# ADCS.net
KiCad netlist of a schematic drawn in Altium Designer
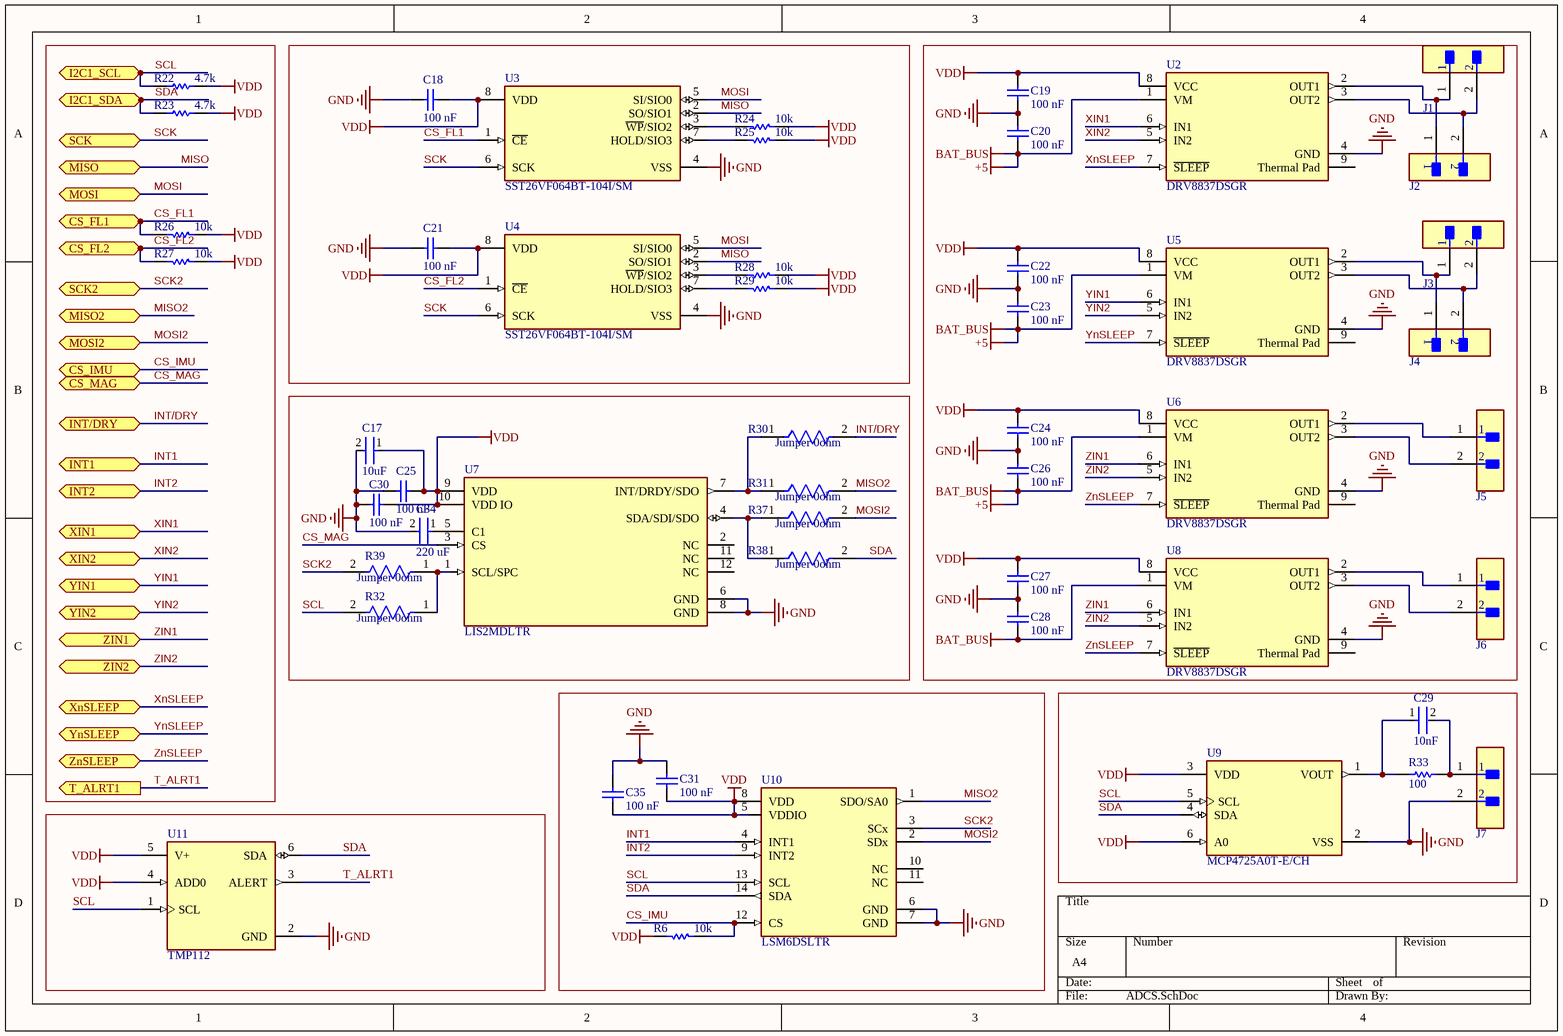
[diagram p0: ADCS.SchDoc]

(export (version "E")
  (design (tool "Eeschema 10.0.6"))
  (components
    (comp (ref "C17")
      (value "10uF")
      (footprint "FP-CL21B106KOQNNNG-MFG")
      (description "CAP CER 10UF 16V X7R 0805")
      (fields (field (name "TOLERANCE") "10%") (field (name "MANUFACTURER PART NUMBER") "CL21B106KOQNNNG"))
      (libsource (lib "Altium Content Vault") (part "b4654b650e69147ec39a6b967a45e02"))
    )
    (comp (ref "C18")
      (value "100 nF")
      (footprint "CAPC1050X55X23ML05T13")
      (description "Chip Capacitor, 100 nF, +/- 10%, 16 V, -55 to 125 degC, 0402 (1005 Metric), RoHS, Tape and Reel")
      (fields (field (name "MANUFACTURER") "Samsung Electro-Mechanics"))
      (libsource (lib "Altium Content Vault") (part "CAP-NP-2"))
    )
    (comp (ref "C19")
      (value "100 nF")
      (footprint "CAPC1050X55X23ML05T13")
      (description "Chip Capacitor, 100 nF, +/- 10%, 16 V, -55 to 125 degC, 0402 (1005 Metric), RoHS, Tape and Reel")
      (fields (field (name "MANUFACTURER") "Samsung Electro-Mechanics"))
      (libsource (lib "Altium Content Vault") (part "CAP-NP-2"))
    )
    (comp (ref "C20")
      (value "100 nF")
      (footprint "CAPC1050X55X23ML05T13")
      (description "Chip Capacitor, 100 nF, +/- 10%, 16 V, -55 to 125 degC, 0402 (1005 Metric), RoHS, Tape and Reel")
      (fields (field (name "MANUFACTURER") "Samsung Electro-Mechanics"))
      (libsource (lib "Altium Content Vault") (part "CAP-NP-2"))
    )
    (comp (ref "C21")
      (value "100 nF")
      (footprint "CAPC1050X55X23ML05T13")
      (description "Chip Capacitor, 100 nF, +/- 10%, 16 V, -55 to 125 degC, 0402 (1005 Metric), RoHS, Tape and Reel")
      (fields (field (name "MANUFACTURER") "Samsung Electro-Mechanics"))
      (libsource (lib "Altium Content Vault") (part "CAP-NP-2"))
    )
    (comp (ref "C22")
      (value "100 nF")
      (footprint "CAPC1050X55X23ML05T13")
      (description "Chip Capacitor, 100 nF, +/- 10%, 16 V, -55 to 125 degC, 0402 (1005 Metric), RoHS, Tape and Reel")
      (fields (field (name "MANUFACTURER") "Samsung Electro-Mechanics"))
      (libsource (lib "Altium Content Vault") (part "CAP-NP-2"))
    )
    (comp (ref "C23")
      (value "100 nF")
      (footprint "CAPC1050X55X23ML05T13")
      (description "Chip Capacitor, 100 nF, +/- 10%, 16 V, -55 to 125 degC, 0402 (1005 Metric), RoHS, Tape and Reel")
      (fields (field (name "MANUFACTURER") "Samsung Electro-Mechanics"))
      (libsource (lib "Altium Content Vault") (part "CAP-NP-2"))
    )
    (comp (ref "C24")
      (value "100 nF")
      (footprint "CAPC1050X55X23ML05T13")
      (description "Chip Capacitor, 100 nF, +/- 10%, 16 V, -55 to 125 degC, 0402 (1005 Metric), RoHS, Tape and Reel")
      (fields (field (name "MANUFACTURER") "Samsung Electro-Mechanics"))
      (libsource (lib "Altium Content Vault") (part "CAP-NP-2"))
    )
    (comp (ref "C25")
      (value "100 nF")
      (footprint "CAPC1050X55X23ML05T13")
      (description "Chip Capacitor, 100 nF, +/- 10%, 16 V, -55 to 125 degC, 0402 (1005 Metric), RoHS, Tape and Reel")
      (fields (field (name "MANUFACTURER") "Samsung Electro-Mechanics"))
      (libsource (lib "Altium Content Vault") (part "CAP-NP-2"))
    )
    (comp (ref "C26")
      (value "100 nF")
      (footprint "CAPC1050X55X23ML05T13")
      (description "Chip Capacitor, 100 nF, +/- 10%, 16 V, -55 to 125 degC, 0402 (1005 Metric), RoHS, Tape and Reel")
      (fields (field (name "MANUFACTURER") "Samsung Electro-Mechanics"))
      (libsource (lib "Altium Content Vault") (part "CAP-NP-2"))
    )
    (comp (ref "C27")
      (value "100 nF")
      (footprint "CAPC1050X55X23ML05T13")
      (description "Chip Capacitor, 100 nF, +/- 10%, 16 V, -55 to 125 degC, 0402 (1005 Metric), RoHS, Tape and Reel")
      (fields (field (name "MANUFACTURER") "Samsung Electro-Mechanics"))
      (libsource (lib "Altium Content Vault") (part "CAP-NP-2"))
    )
    (comp (ref "C28")
      (value "100 nF")
      (footprint "CAPC1050X55X23ML05T13")
      (description "Chip Capacitor, 100 nF, +/- 10%, 16 V, -55 to 125 degC, 0402 (1005 Metric), RoHS, Tape and Reel")
      (fields (field (name "MANUFACTURER") "Samsung Electro-Mechanics"))
      (libsource (lib "Altium Content Vault") (part "CAP-NP-2"))
    )
    (comp (ref "C29")
      (value "10nF")
      (footprint "FP-CL165-IPC_C")
      (description "Cap Ceramic 10nF 50V X7R ±10% SMD 0402 +125°C Paper T/R")
      (fields (field (name "VOLTAGE") "50V") (field (name "TOLERANCE") "10%"))
      (libsource (lib "Altium Content Vault") (part "b4654b650e69147ec39a6b967a45e02"))
    )
    (comp (ref "C30")
      (value "100 nF")
      (footprint "CAPC1050X55X23ML05T13")
      (description "Chip Capacitor, 100 nF, +/- 10%, 16 V, -55 to 125 degC, 0402 (1005 Metric), RoHS, Tape and Reel")
      (fields (field (name "MANUFACTURER") "Samsung Electro-Mechanics"))
      (libsource (lib "Altium Content Vault") (part "CAP-NP-2"))
    )
    (comp (ref "C31")
      (value "100 nF")
      (footprint "CAPC1050X55X23ML05T13")
      (description "Chip Capacitor, 100 nF, +/- 10%, 16 V, -55 to 125 degC, 0402 (1005 Metric), RoHS, Tape and Reel")
      (fields (field (name "MANUFACTURER") "Samsung Electro-Mechanics"))
      (libsource (lib "Altium Content Vault") (part "CAP-NP-2"))
    )
    (comp (ref "C34")
      (value "220 uF")
      (footprint "FP-C0603C-CF-MFG")
      (description "CAP CER 0603 .22UF 10V X7R 20% A")
      (fields (field (name "TOLERANCE") "0.2") (field (name "MANUFACTURER PART NUMBER") "C0603C224M8RACAUTO"))
      (libsource (lib "Altium Content Vault") (part "b4654b650e69147ec39a6b967a45e02"))
    )
    (comp (ref "C35")
      (value "100 nF")
      (footprint "CAPC1050X55X23ML05T13")
      (description "Chip Capacitor, 100 nF, +/- 10%, 16 V, -55 to 125 degC, 0402 (1005 Metric), RoHS, Tape and Reel")
      (fields (field (name "MANUFACTURER") "Samsung Electro-Mechanics"))
      (libsource (lib "Altium Content Vault") (part "CAP-NP-2"))
    )
    (comp (ref "J1")
      (value "B2B-XH-A(LF)(SN)")
      (footprint "FP-B2B-XH-A_LF_SN-MFG")
      (description "CONN HEADER VERT 2POS 2.5MM")
      (libsource (lib "") (part "3bc925449376181038e59eaffc5286c_1"))
    )
    (comp (ref "J2")
      (value "B2B-XH-A(LF)(SN)")
      (footprint "FP-B2B-XH-A_LF_SN-MFG")
      (description "CONN HEADER VERT 2POS 2.5MM")
      (libsource (lib "") (part "3bc925449376181038e59eaffc5286c_2"))
    )
    (comp (ref "J3")
      (value "B2B-XH-A(LF)(SN)")
      (footprint "FP-B2B-XH-A_LF_SN-MFG")
      (description "CONN HEADER VERT 2POS 2.5MM")
      (libsource (lib "") (part "3bc925449376181038e59eaffc5286c_1"))
    )
    (comp (ref "J4")
      (value "B2B-XH-A(LF)(SN)")
      (footprint "FP-B2B-XH-A_LF_SN-MFG")
      (description "CONN HEADER VERT 2POS 2.5MM")
      (libsource (lib "") (part "3bc925449376181038e59eaffc5286c_2"))
    )
    (comp (ref "J5")
      (value "B2B-XH-A(LF)(SN)")
      (footprint "FP-B2B-XH-A_LF_SN-MFG")
      (description "CONN HEADER VERT 2POS 2.5MM")
      (libsource (lib "Altium Content Vault") (part "3bc925449376181038e59eaffc5286c"))
    )
    (comp (ref "J6")
      (value "B2B-XH-A(LF)(SN)")
      (footprint "FP-B2B-XH-A_LF_SN-MFG")
      (description "CONN HEADER VERT 2POS 2.5MM")
      (libsource (lib "Altium Content Vault") (part "3bc925449376181038e59eaffc5286c"))
    )
    (comp (ref "J7")
      (value "B2B-XH-A(LF)(SN)")
      (footprint "FP-B2B-XH-A_LF_SN-MFG")
      (description "CONN HEADER VERT 2POS 2.5MM")
      (libsource (lib "Altium Content Vault") (part "3bc925449376181038e59eaffc5286c"))
    )
    (comp (ref "R6")
      (value "10k")
      (footprint "RESC1005X40X25LL05T05")
      (description "Chip Resistor, 10 KOhm, +/- 1%, 0.1 W, -55 to 155 degC, 0402 (1005 Metric), RoHS, Tape and Reel")
      (fields (field (name "TOLERANCE") "1%") (field (name "MANUFACTURER") "Panasonic"))
      (libsource (lib "Altium Content Vault") (part "RES-2"))
    )
    (comp (ref "R22")
      (value "4.7k")
      (footprint "RESC1005X40X25LL05T05")
      (description "Chip Resistor, 4.7 KOhm, +/- 1%, 0.1 W, -55 to 155 degC, 0402 (1005 Metric), RoHS, Tape and Reel")
      (fields (field (name "TOLERANCE") "1%") (field (name "PARTNUMBER") "ERJ-2RKF4701X"))
      (libsource (lib "Altium Content Vault") (part "RES-2"))
    )
    (comp (ref "R23")
      (value "4.7k")
      (footprint "RESC1005X40X25LL05T05")
      (description "Chip Resistor, 4.7 KOhm, +/- 1%, 0.1 W, -55 to 155 degC, 0402 (1005 Metric), RoHS, Tape and Reel")
      (fields (field (name "TOLERANCE") "1%") (field (name "PARTNUMBER") "ERJ-2RKF4701X"))
      (libsource (lib "Altium Content Vault") (part "RES-2"))
    )
    (comp (ref "R24")
      (value "10k")
      (footprint "RESC1005X40X25LL05T05")
      (description "Chip Resistor, 10 KOhm, +/- 1%, 0.1 W, -55 to 155 degC, 0402 (1005 Metric), RoHS, Tape and Reel")
      (fields (field (name "TOLERANCE") "1%") (field (name "MANUFACTURER") "Panasonic"))
      (libsource (lib "Altium Content Vault") (part "RES-2"))
    )
    (comp (ref "R25")
      (value "10k")
      (footprint "RESC1005X40X25LL05T05")
      (description "Chip Resistor, 10 KOhm, +/- 1%, 0.1 W, -55 to 155 degC, 0402 (1005 Metric), RoHS, Tape and Reel")
      (fields (field (name "TOLERANCE") "1%") (field (name "MANUFACTURER") "Panasonic"))
      (libsource (lib "Altium Content Vault") (part "RES-2"))
    )
    (comp (ref "R26")
      (value "10k")
      (footprint "RESC1005X40X25LL05T05")
      (description "Chip Resistor, 10 KOhm, +/- 1%, 0.1 W, -55 to 155 degC, 0402 (1005 Metric), RoHS, Tape and Reel")
      (fields (field (name "TOLERANCE") "1%") (field (name "MANUFACTURER") "Panasonic"))
      (libsource (lib "Altium Content Vault") (part "RES-2"))
    )
    (comp (ref "R27")
      (value "10k")
      (footprint "RESC1005X40X25LL05T05")
      (description "Chip Resistor, 10 KOhm, +/- 1%, 0.1 W, -55 to 155 degC, 0402 (1005 Metric), RoHS, Tape and Reel")
      (fields (field (name "TOLERANCE") "1%") (field (name "MANUFACTURER") "Panasonic"))
      (libsource (lib "Altium Content Vault") (part "RES-2"))
    )
    (comp (ref "R28")
      (value "10k")
      (footprint "RESC1005X40X25LL05T05")
      (description "Chip Resistor, 10 KOhm, +/- 1%, 0.1 W, -55 to 155 degC, 0402 (1005 Metric), RoHS, Tape and Reel")
      (fields (field (name "TOLERANCE") "1%") (field (name "MANUFACTURER") "Panasonic"))
      (libsource (lib "Altium Content Vault") (part "RES-2"))
    )
    (comp (ref "R29")
      (value "10k")
      (footprint "RESC1005X40X25LL05T05")
      (description "Chip Resistor, 10 KOhm, +/- 1%, 0.1 W, -55 to 155 degC, 0402 (1005 Metric), RoHS, Tape and Reel")
      (fields (field (name "TOLERANCE") "1%") (field (name "MANUFACTURER") "Panasonic"))
      (libsource (lib "Altium Content Vault") (part "RES-2"))
    )
    (comp (ref "R30")
      (value "Jumper 0ohm")
      (footprint "FP-RC1206-MFG")
      (description "RES SMD 0 OHM JUMPER 1/4W 1206")
      (fields
        (field (name "MANUFACTURER PART NUMBER") "RC1206JR-070RL")
        (field (name "MANUFACTURER") "YAGEO")
      )
      (libsource (lib "Altium Content Vault") (part "1029c3af85768c4190bb7ad29bc67b5"))
    )
    (comp (ref "R31")
      (value "Jumper 0ohm")
      (footprint "FP-RC1206-MFG")
      (description "RES SMD 0 OHM JUMPER 1/4W 1206")
      (fields
        (field (name "MANUFACTURER PART NUMBER") "RC1206JR-070RL")
        (field (name "MANUFACTURER") "YAGEO")
      )
      (libsource (lib "Altium Content Vault") (part "1029c3af85768c4190bb7ad29bc67b5"))
    )
    (comp (ref "R32")
      (value "Jumper 0ohm")
      (footprint "FP-RC1206-MFG")
      (description "RES SMD 0 OHM JUMPER 1/4W 1206")
      (fields
        (field (name "MANUFACTURER PART NUMBER") "RC1206JR-070RL")
        (field (name "MANUFACTURER") "YAGEO")
      )
      (libsource (lib "Altium Content Vault") (part "1029c3af85768c4190bb7ad29bc67b5"))
    )
    (comp (ref "R33")
      (value "100")
      (footprint "RESC1608X55X30LL15T15")
      (fields (field (name "MANUFACTURER") "Panasonic") (field (name "PART NUMBER") "ERJ-3EKF1000V"))
      (libsource (lib "Altium Content Vault") (part "RES"))
    )
    (comp (ref "R37")
      (value "Jumper 0ohm")
      (footprint "FP-RC1206-MFG")
      (description "RES SMD 0 OHM JUMPER 1/4W 1206")
      (fields
        (field (name "MANUFACTURER PART NUMBER") "RC1206JR-070RL")
        (field (name "MANUFACTURER") "YAGEO")
      )
      (libsource (lib "Altium Content Vault") (part "1029c3af85768c4190bb7ad29bc67b5"))
    )
    (comp (ref "R38")
      (value "Jumper 0ohm")
      (footprint "FP-RC1206-MFG")
      (description "RES SMD 0 OHM JUMPER 1/4W 1206")
      (fields
        (field (name "MANUFACTURER PART NUMBER") "RC1206JR-070RL")
        (field (name "MANUFACTURER") "YAGEO")
      )
      (libsource (lib "Altium Content Vault") (part "1029c3af85768c4190bb7ad29bc67b5"))
    )
    (comp (ref "R39")
      (value "Jumper 0ohm")
      (footprint "FP-RC1206-MFG")
      (description "RES SMD 0 OHM JUMPER 1/4W 1206")
      (fields
        (field (name "MANUFACTURER PART NUMBER") "RC1206JR-070RL")
        (field (name "MANUFACTURER") "YAGEO")
      )
      (libsource (lib "Altium Content Vault") (part "1029c3af85768c4190bb7ad29bc67b5"))
    )
    (comp (ref "U2")
      (value "DRV8837DSGR")
      (footprint "FP-DSG0008A-MFG")
      (description "IC MOTOR DRIVER PAR 8WSON")
      (fields
        (field (name "MANUFACTURER") "Texas Instruments")
        (field (name "OCTOPART") "https://octopart.com/drv8837dsgr-texas+instruments-23786726")
      )
      (libsource (lib "Altium Content Vault") (part "0edabe62f55b79d65ef7cb8a22a7164"))
    )
    (comp (ref "U3")
      (value "SST26VF064BT-104I/SM")
      (footprint "FP-C04-056-IPC_A")
      (description "IC FLASH 64M SPI 104MHZ 8SOIJ")
      (libsource (lib "Altium Content Vault") (part "6350b331e85e90157e4ee501ce7d1a5"))
    )
    (comp (ref "U4")
      (value "SST26VF064BT-104I/SM")
      (footprint "FP-C04-056-IPC_A")
      (description "IC FLASH 64M SPI 104MHZ 8SOIJ")
      (libsource (lib "Altium Content Vault") (part "6350b331e85e90157e4ee501ce7d1a5"))
    )
    (comp (ref "U5")
      (value "DRV8837DSGR")
      (footprint "FP-DSG0008A-MFG")
      (description "IC MOTOR DRIVER PAR 8WSON")
      (fields
        (field (name "MANUFACTURER") "Texas Instruments")
        (field (name "OCTOPART") "https://octopart.com/drv8837dsgr-texas+instruments-23786726")
      )
      (libsource (lib "Altium Content Vault") (part "0edabe62f55b79d65ef7cb8a22a7164"))
    )
    (comp (ref "U6")
      (value "DRV8837DSGR")
      (footprint "FP-DSG0008A-MFG")
      (description "IC MOTOR DRIVER PAR 8WSON")
      (fields
        (field (name "MANUFACTURER") "Texas Instruments")
        (field (name "OCTOPART") "https://octopart.com/drv8837dsgr-texas+instruments-23786726")
      )
      (libsource (lib "Altium Content Vault") (part "0edabe62f55b79d65ef7cb8a22a7164"))
    )
    (comp (ref "U7")
      (value "LIS2MDLTR")
      (footprint "FP-LGA-12-DM00170568-MFG")
      (description "SENSOR MR I2C/SPI 12LGA")
      (fields
        (field (name "OCTOPART") "https://octopart.com/lis2mdltr-stmicroelectronics-81117311")
        (field (name "MANUFACTURER") "STMicroelectronics")
      )
      (libsource (lib "Altium Content Vault") (part "91637d6a6da3cb2d69b1e7726cd74d2"))
    )
    (comp (ref "U8")
      (value "DRV8837DSGR")
      (footprint "FP-DSG0008A-MFG")
      (description "IC MOTOR DRIVER PAR 8WSON")
      (fields
        (field (name "MANUFACTURER") "Texas Instruments")
        (field (name "OCTOPART") "https://octopart.com/drv8837dsgr-texas+instruments-23786726")
      )
      (libsource (lib "Altium Content Vault") (part "0edabe62f55b79d65ef7cb8a22a7164"))
    )
    (comp (ref "U9")
      (value "MCP4725A0T-E/CH")
      (footprint "FP-C04-028-CHY-IPC_A")
      (description "IC DAC 12BIT V-OUT SOT23-6")
      (libsource (lib "Altium Content Vault") (part "13d1b9b03173b6bd00baa384b893ce8"))
    )
    (comp (ref "U10")
      (value "LSM6DSLTR")
      (footprint "FP-LGA-14L-DM00249496-MFG")
      (description "IMU ACCEL/GYRO I2C/SPI 14LGA")
      (fields
        (field (name "MANUFACTURER") "STMicroelectronics")
        (field (name "OCTOPART") "https://octopart.com/lsm6dsltr-stmicroelectronics-66358193")
      )
      (libsource (lib "Altium Content Vault") (part "4e27e7d1829efda5344af1708d65448"))
    )
    (comp (ref "U11")
      (value "TMP112")
      (footprint "FP-DRL0006A-MFG")
      (description "SENSOR DIGITAL -40C-125C 6SOT \r\nTMP112AIDRLR, NOT AQDRLRQ1")
      (fields
        (field (name "OCTOPART") "https://octopart.com/tmp112aqdrlrq1-texas+instruments-50418097")
        (field (name "MANUFACTURER") "Texas Instruments")
      )
      (libsource (lib "Altium Content Vault") (part "df8922b65016335707baceee56509f2"))
    )
  )
  (nets
    (net (code "1") (name "+5") (class "Default")
      (node (ref "C20") (pin "1") (pinfunction "1_1") (pintype "passive"))
      (node (ref "C23") (pin "1") (pinfunction "1_1") (pintype "passive"))
      (node (ref "C26") (pin "1") (pinfunction "1_1") (pintype "passive"))
      (node (ref "C28") (pin "1") (pinfunction "1_1") (pintype "passive"))
      (node (ref "U2") (pin "1") (pinfunction "VM_1") (pintype "power_in"))
      (node (ref "U5") (pin "1") (pinfunction "VM_1") (pintype "power_in"))
      (node (ref "U6") (pin "1") (pinfunction "VM_1") (pintype "power_in"))
      (node (ref "U8") (pin "1") (pinfunction "VM_1") (pintype "power_in"))
    )
    (net (code "2") (name "/CS_FL1") (class "Default")
      (node (ref "R26") (pin "2") (pinfunction "2_2") (pintype "passive"))
      (node (ref "U3") (pin "1") (pinfunction "~{CE}_1") (pintype "input"))
    )
    (net (code "3") (name "/CS_FL2") (class "Default")
      (node (ref "R27") (pin "2") (pinfunction "2_2") (pintype "passive"))
      (node (ref "U4") (pin "1") (pinfunction "~{CE}_1") (pintype "input"))
    )
    (net (code "4") (name "/CS_IMU") (class "Default")
      (node (ref "R6") (pin "1") (pinfunction "1_1") (pintype "passive"))
      (node (ref "U10") (pin "12") (pinfunction "CS_12") (pintype "input"))
    )
    (net (code "5") (name "/CS_MAG") (class "Default")
      (node (ref "U7") (pin "3") (pinfunction "CS_3") (pintype "input"))
    )
    (net (code "6") (name "/INT1") (class "Default")
      (node (ref "U10") (pin "4") (pinfunction "INT1_4") (pintype "input"))
    )
    (net (code "7") (name "/INT2") (class "Default")
      (node (ref "U10") (pin "9") (pinfunction "INT2_9") (pintype "input"))
    )
    (net (code "8") (name "/INT{slash}DRY") (class "Default")
      (node (ref "R30") (pin "2") (pinfunction "2_2") (pintype "passive"))
    )
    (net (code "9") (name "/MISO") (class "Default")
      (node (ref "U3") (pin "2") (pinfunction "SO/SIO1_2") (pintype "bidirectional"))
      (node (ref "U4") (pin "2") (pinfunction "SO/SIO1_2") (pintype "bidirectional"))
    )
    (net (code "10") (name "/MISO2") (class "Default")
      (node (ref "R31") (pin "2") (pinfunction "2_2") (pintype "passive"))
      (node (ref "U10") (pin "1") (pinfunction "SDO/SA0_1") (pintype "output"))
    )
    (net (code "11") (name "/MOSI") (class "Default")
      (node (ref "U3") (pin "5") (pinfunction "SI/SIO0_5") (pintype "bidirectional"))
      (node (ref "U4") (pin "5") (pinfunction "SI/SIO0_5") (pintype "bidirectional"))
    )
    (net (code "12") (name "/MOSI2") (class "Default")
      (node (ref "R37") (pin "2") (pinfunction "2_2") (pintype "passive"))
      (node (ref "U10") (pin "2") (pinfunction "SDx_2") (pintype "passive"))
    )
    (net (code "13") (name "/SCK") (class "Default")
      (node (ref "U3") (pin "6") (pinfunction "SCK_6") (pintype "input"))
      (node (ref "U4") (pin "6") (pinfunction "SCK_6") (pintype "input"))
    )
    (net (code "14") (name "/SCK2") (class "Default")
      (node (ref "R39") (pin "2") (pinfunction "2_2") (pintype "passive"))
      (node (ref "U10") (pin "3") (pinfunction "SCx_3") (pintype "passive"))
    )
    (net (code "15") (name "/SCL") (class "Default")
      (node (ref "R22") (pin "1") (pinfunction "1_1") (pintype "passive"))
      (node (ref "R32") (pin "2") (pinfunction "2_2") (pintype "passive"))
      (node (ref "U10") (pin "13") (pinfunction "SCL_13") (pintype "input"))
      (node (ref "U11") (pin "1") (pinfunction "SCL_1") (pintype "input"))
      (node (ref "U9") (pin "5") (pinfunction "SCL_5") (pintype "input"))
    )
    (net (code "16") (name "/SDA") (class "Default")
      (node (ref "R23") (pin "1") (pinfunction "1_1") (pintype "passive"))
      (node (ref "R38") (pin "2") (pinfunction "2_2") (pintype "passive"))
      (node (ref "U10") (pin "14") (pinfunction "SDA_14") (pintype "output"))
      (node (ref "U11") (pin "6") (pinfunction "SDA_6") (pintype "bidirectional"))
      (node (ref "U9") (pin "4") (pinfunction "SDA_4") (pintype "bidirectional"))
    )
    (net (code "17") (name "/T_ALRT1") (class "Default")
      (node (ref "U11") (pin "3") (pinfunction "ALERT_3") (pintype "output"))
    )
    (net (code "18") (name "/XIN1") (class "Default")
      (node (ref "U2") (pin "6") (pinfunction "IN1_6") (pintype "input"))
    )
    (net (code "19") (name "/XIN2") (class "Default")
      (node (ref "U2") (pin "5") (pinfunction "IN2_5") (pintype "input"))
    )
    (net (code "20") (name "/XnSLEEP") (class "Default")
      (node (ref "U2") (pin "7") (pinfunction "~{SLEEP}_7") (pintype "input"))
    )
    (net (code "21") (name "/YIN1") (class "Default")
      (node (ref "U5") (pin "6") (pinfunction "IN1_6") (pintype "input"))
    )
    (net (code "22") (name "/YIN2") (class "Default")
      (node (ref "U5") (pin "5") (pinfunction "IN2_5") (pintype "input"))
    )
    (net (code "23") (name "/YnSLEEP") (class "Default")
      (node (ref "U5") (pin "7") (pinfunction "~{SLEEP}_7") (pintype "input"))
    )
    (net (code "24") (name "/ZIN1") (class "Default")
      (node (ref "U6") (pin "6") (pinfunction "IN1_6") (pintype "input"))
      (node (ref "U8") (pin "6") (pinfunction "IN1_6") (pintype "input"))
    )
    (net (code "25") (name "/ZIN2") (class "Default")
      (node (ref "U6") (pin "5") (pinfunction "IN2_5") (pintype "input"))
      (node (ref "U8") (pin "5") (pinfunction "IN2_5") (pintype "input"))
    )
    (net (code "26") (name "/ZnSLEEP") (class "Default")
      (node (ref "U6") (pin "7") (pinfunction "~{SLEEP}_7") (pintype "input"))
      (node (ref "U8") (pin "7") (pinfunction "~{SLEEP}_7") (pintype "input"))
    )
    (net (code "27") (name "GND") (class "Default")
      (node (ref "C17") (pin "2") (pinfunction "2_2") (pintype "passive"))
      (node (ref "C18") (pin "1") (pinfunction "1_1") (pintype "passive"))
      (node (ref "C19") (pin "2") (pinfunction "2_2") (pintype "passive"))
      (node (ref "C20") (pin "2") (pinfunction "2_2") (pintype "passive"))
      (node (ref "C21") (pin "1") (pinfunction "1_1") (pintype "passive"))
      (node (ref "C22") (pin "2") (pinfunction "2_2") (pintype "passive"))
      (node (ref "C23") (pin "2") (pinfunction "2_2") (pintype "passive"))
      (node (ref "C24") (pin "2") (pinfunction "2_2") (pintype "passive"))
      (node (ref "C25") (pin "1") (pinfunction "1_1") (pintype "passive"))
      (node (ref "C26") (pin "2") (pinfunction "2_2") (pintype "passive"))
      (node (ref "C27") (pin "2") (pinfunction "2_2") (pintype "passive"))
      (node (ref "C28") (pin "2") (pinfunction "2_2") (pintype "passive"))
      (node (ref "C30") (pin "1") (pinfunction "1_1") (pintype "passive"))
      (node (ref "C31") (pin "2") (pinfunction "2_2") (pintype "passive"))
      (node (ref "C34") (pin "2") (pinfunction "2_2") (pintype "passive"))
      (node (ref "C35") (pin "2") (pinfunction "2_2") (pintype "passive"))
      (node (ref "J7") (pin "2") (pinfunction "2_2") (pintype "passive"))
      (node (ref "U10") (pin "6") (pinfunction "GND_6") (pintype "power_in"))
      (node (ref "U10") (pin "7") (pinfunction "GND_7") (pintype "power_in"))
      (node (ref "U11") (pin "2") (pinfunction "GND_2") (pintype "power_in"))
      (node (ref "U2") (pin "4") (pinfunction "GND_4") (pintype "power_in"))
      (node (ref "U3") (pin "4") (pinfunction "VSS_4") (pintype "power_in"))
      (node (ref "U4") (pin "4") (pinfunction "VSS_4") (pintype "power_in"))
      (node (ref "U5") (pin "4") (pinfunction "GND_4") (pintype "power_in"))
      (node (ref "U6") (pin "4") (pinfunction "GND_4") (pintype "power_in"))
      (node (ref "U7") (pin "6") (pinfunction "GND_6") (pintype "power_in"))
      (node (ref "U7") (pin "8") (pinfunction "GND_8") (pintype "power_in"))
      (node (ref "U8") (pin "4") (pinfunction "GND_4") (pintype "power_in"))
      (node (ref "U9") (pin "2") (pinfunction "VSS_2") (pintype "power_in"))
    )
    (net (code "28") (name "Net-(C29-Pad2)") (class "Default")
      (node (ref "C29") (pin "2") (pinfunction "2_2") (pintype "passive"))
      (node (ref "J7") (pin "1") (pinfunction "1_1") (pintype "passive"))
      (node (ref "R33") (pin "2") (pinfunction "2_2") (pintype "passive"))
    )
    (net (code "29") (name "Net-(U2-OUT1)") (class "Default")
      (node (ref "J1") (pin "1") (pinfunction "1_1") (pintype "passive"))
      (node (ref "J2") (pin "1") (pinfunction "1_1") (pintype "passive"))
      (node (ref "U2") (pin "2") (pinfunction "OUT1_2") (pintype "output"))
    )
    (net (code "30") (name "Net-(U2-OUT2)") (class "Default")
      (node (ref "J1") (pin "2") (pinfunction "2_2") (pintype "passive"))
      (node (ref "J2") (pin "2") (pinfunction "2_2") (pintype "passive"))
      (node (ref "U2") (pin "3") (pinfunction "OUT2_3") (pintype "output"))
    )
    (net (code "31") (name "Net-(U3-HOLD{slash}SIO3)") (class "Default")
      (node (ref "R25") (pin "2") (pinfunction "2_2") (pintype "passive"))
      (node (ref "U3") (pin "7") (pinfunction "HOLD/SIO3_7") (pintype "bidirectional"))
    )
    (net (code "32") (name "Net-(U3-~{WP}{slash}SIO2)") (class "Default")
      (node (ref "R24") (pin "2") (pinfunction "2_2") (pintype "passive"))
      (node (ref "U3") (pin "3") (pinfunction "~{WP}/SIO2_3") (pintype "bidirectional"))
    )
    (net (code "33") (name "Net-(U4-HOLD{slash}SIO3)") (class "Default")
      (node (ref "R29") (pin "2") (pinfunction "2_2") (pintype "passive"))
      (node (ref "U4") (pin "7") (pinfunction "HOLD/SIO3_7") (pintype "bidirectional"))
    )
    (net (code "34") (name "Net-(U4-~{WP}{slash}SIO2)") (class "Default")
      (node (ref "R28") (pin "2") (pinfunction "2_2") (pintype "passive"))
      (node (ref "U4") (pin "3") (pinfunction "~{WP}/SIO2_3") (pintype "bidirectional"))
    )
    (net (code "35") (name "Net-(U5-OUT1)") (class "Default")
      (node (ref "J3") (pin "1") (pinfunction "1_1") (pintype "passive"))
      (node (ref "J4") (pin "1") (pinfunction "1_1") (pintype "passive"))
      (node (ref "U5") (pin "2") (pinfunction "OUT1_2") (pintype "output"))
    )
    (net (code "36") (name "Net-(U5-OUT2)") (class "Default")
      (node (ref "J3") (pin "2") (pinfunction "2_2") (pintype "passive"))
      (node (ref "J4") (pin "2") (pinfunction "2_2") (pintype "passive"))
      (node (ref "U5") (pin "3") (pinfunction "OUT2_3") (pintype "output"))
    )
    (net (code "37") (name "Net-(U6-OUT1)") (class "Default")
      (node (ref "J5") (pin "1") (pinfunction "1_1") (pintype "passive"))
      (node (ref "U6") (pin "2") (pinfunction "OUT1_2") (pintype "output"))
    )
    (net (code "38") (name "Net-(U6-OUT2)") (class "Default")
      (node (ref "J5") (pin "2") (pinfunction "2_2") (pintype "passive"))
      (node (ref "U6") (pin "3") (pinfunction "OUT2_3") (pintype "output"))
    )
    (net (code "39") (name "Net-(U7-C1)") (class "Default")
      (node (ref "C34") (pin "1") (pinfunction "1_1") (pintype "passive"))
      (node (ref "U7") (pin "5") (pinfunction "C1_5") (pintype "passive"))
    )
    (net (code "40") (name "Net-(U7-INT{slash}DRDY{slash}SDO)") (class "Default")
      (node (ref "R30") (pin "1") (pinfunction "1_1") (pintype "passive"))
      (node (ref "R31") (pin "1") (pinfunction "1_1") (pintype "passive"))
      (node (ref "U7") (pin "7") (pinfunction "INT/DRDY/SDO_7") (pintype "output"))
    )
    (net (code "41") (name "Net-(U7-SCL{slash}SPC)") (class "Default")
      (node (ref "R32") (pin "1") (pinfunction "1_1") (pintype "passive"))
      (node (ref "R39") (pin "1") (pinfunction "1_1") (pintype "passive"))
      (node (ref "U7") (pin "1") (pinfunction "SCL/SPC_1") (pintype "input"))
    )
    (net (code "42") (name "Net-(U7-SDA{slash}SDI{slash}SDO)") (class "Default")
      (node (ref "R37") (pin "1") (pinfunction "1_1") (pintype "passive"))
      (node (ref "R38") (pin "1") (pinfunction "1_1") (pintype "passive"))
      (node (ref "U7") (pin "4") (pinfunction "SDA/SDI/SDO_4") (pintype "bidirectional"))
    )
    (net (code "43") (name "Net-(U8-OUT1)") (class "Default")
      (node (ref "J6") (pin "1") (pinfunction "1_1") (pintype "passive"))
      (node (ref "U8") (pin "2") (pinfunction "OUT1_2") (pintype "output"))
    )
    (net (code "44") (name "Net-(U8-OUT2)") (class "Default")
      (node (ref "J6") (pin "2") (pinfunction "2_2") (pintype "passive"))
      (node (ref "U8") (pin "3") (pinfunction "OUT2_3") (pintype "output"))
    )
    (net (code "45") (name "Net-(U9-VOUT)") (class "Default")
      (node (ref "C29") (pin "1") (pinfunction "1_1") (pintype "passive"))
      (node (ref "R33") (pin "1") (pinfunction "1_1") (pintype "passive"))
      (node (ref "U9") (pin "1") (pinfunction "VOUT_1") (pintype "output"))
    )
    (net (code "46") (name "VDD") (class "Default")
      (node (ref "C17") (pin "1") (pinfunction "1_1") (pintype "passive"))
      (node (ref "C18") (pin "2") (pinfunction "2_2") (pintype "passive"))
      (node (ref "C19") (pin "1") (pinfunction "1_1") (pintype "passive"))
      (node (ref "C21") (pin "2") (pinfunction "2_2") (pintype "passive"))
      (node (ref "C22") (pin "1") (pinfunction "1_1") (pintype "passive"))
      (node (ref "C24") (pin "1") (pinfunction "1_1") (pintype "passive"))
      (node (ref "C25") (pin "2") (pinfunction "2_2") (pintype "passive"))
      (node (ref "C27") (pin "1") (pinfunction "1_1") (pintype "passive"))
      (node (ref "C30") (pin "2") (pinfunction "2_2") (pintype "passive"))
      (node (ref "C31") (pin "1") (pinfunction "1_1") (pintype "passive"))
      (node (ref "C35") (pin "1") (pinfunction "1_1") (pintype "passive"))
      (node (ref "R22") (pin "2") (pinfunction "2_2") (pintype "passive"))
      (node (ref "R23") (pin "2") (pinfunction "2_2") (pintype "passive"))
      (node (ref "R24") (pin "1") (pinfunction "1_1") (pintype "passive"))
      (node (ref "R25") (pin "1") (pinfunction "1_1") (pintype "passive"))
      (node (ref "R26") (pin "1") (pinfunction "1_1") (pintype "passive"))
      (node (ref "R27") (pin "1") (pinfunction "1_1") (pintype "passive"))
      (node (ref "R28") (pin "1") (pinfunction "1_1") (pintype "passive"))
      (node (ref "R29") (pin "1") (pinfunction "1_1") (pintype "passive"))
      (node (ref "R6") (pin "2") (pinfunction "2_2") (pintype "passive"))
      (node (ref "U10") (pin "5") (pinfunction "VDDIO_5") (pintype "power_in"))
      (node (ref "U10") (pin "8") (pinfunction "VDD_8") (pintype "power_in"))
      (node (ref "U11") (pin "4") (pinfunction "ADD0_4") (pintype "input"))
      (node (ref "U11") (pin "5") (pinfunction "V+_5") (pintype "power_in"))
      (node (ref "U2") (pin "8") (pinfunction "VCC_8") (pintype "power_in"))
      (node (ref "U3") (pin "8") (pinfunction "VDD_8") (pintype "power_in"))
      (node (ref "U4") (pin "8") (pinfunction "VDD_8") (pintype "power_in"))
      (node (ref "U5") (pin "8") (pinfunction "VCC_8") (pintype "power_in"))
      (node (ref "U6") (pin "8") (pinfunction "VCC_8") (pintype "power_in"))
      (node (ref "U7") (pin "10") (pinfunction "VDD_IO_10") (pintype "power_in"))
      (node (ref "U7") (pin "9") (pinfunction "VDD_9") (pintype "power_in"))
      (node (ref "U8") (pin "8") (pinfunction "VCC_8") (pintype "power_in"))
      (node (ref "U9") (pin "3") (pinfunction "VDD_3") (pintype "power_in"))
      (node (ref "U9") (pin "6") (pinfunction "A0_6") (pintype "input"))
    )
    (net (code "47") (name "unconnected-(U2-Thermal_Pad-Pad9)") (class "Default")
      (node (ref "U2") (pin "9") (pinfunction "Thermal_Pad_9") (pintype "power_in"))
    )
    (net (code "48") (name "unconnected-(U5-Thermal_Pad-Pad9)") (class "Default")
      (node (ref "U5") (pin "9") (pinfunction "Thermal_Pad_9") (pintype "power_in"))
    )
    (net (code "49") (name "unconnected-(U6-Thermal_Pad-Pad9)") (class "Default")
      (node (ref "U6") (pin "9") (pinfunction "Thermal_Pad_9") (pintype "power_in"))
    )
    (net (code "50") (name "unconnected-(U7-NC-Pad2)") (class "Default")
      (node (ref "U7") (pin "2") (pinfunction "NC_2") (pintype "passive"))
    )
    (net (code "51") (name "unconnected-(U7-NC-Pad11)") (class "Default")
      (node (ref "U7") (pin "11") (pinfunction "NC_11") (pintype "passive"))
    )
    (net (code "52") (name "unconnected-(U7-NC-Pad12)") (class "Default")
      (node (ref "U7") (pin "12") (pinfunction "NC_12") (pintype "passive"))
    )
    (net (code "53") (name "unconnected-(U8-Thermal_Pad-Pad9)") (class "Default")
      (node (ref "U8") (pin "9") (pinfunction "Thermal_Pad_9") (pintype "power_in"))
    )
    (net (code "54") (name "unconnected-(U10-NC-Pad10)") (class "Default")
      (node (ref "U10") (pin "10") (pinfunction "NC_10") (pintype "passive"))
    )
    (net (code "55") (name "unconnected-(U10-NC-Pad11)") (class "Default")
      (node (ref "U10") (pin "11") (pinfunction "NC_11") (pintype "passive"))
    )
  )
)
